# Controller.net
KiCad netlist of a schematic drawn in Altium Designer
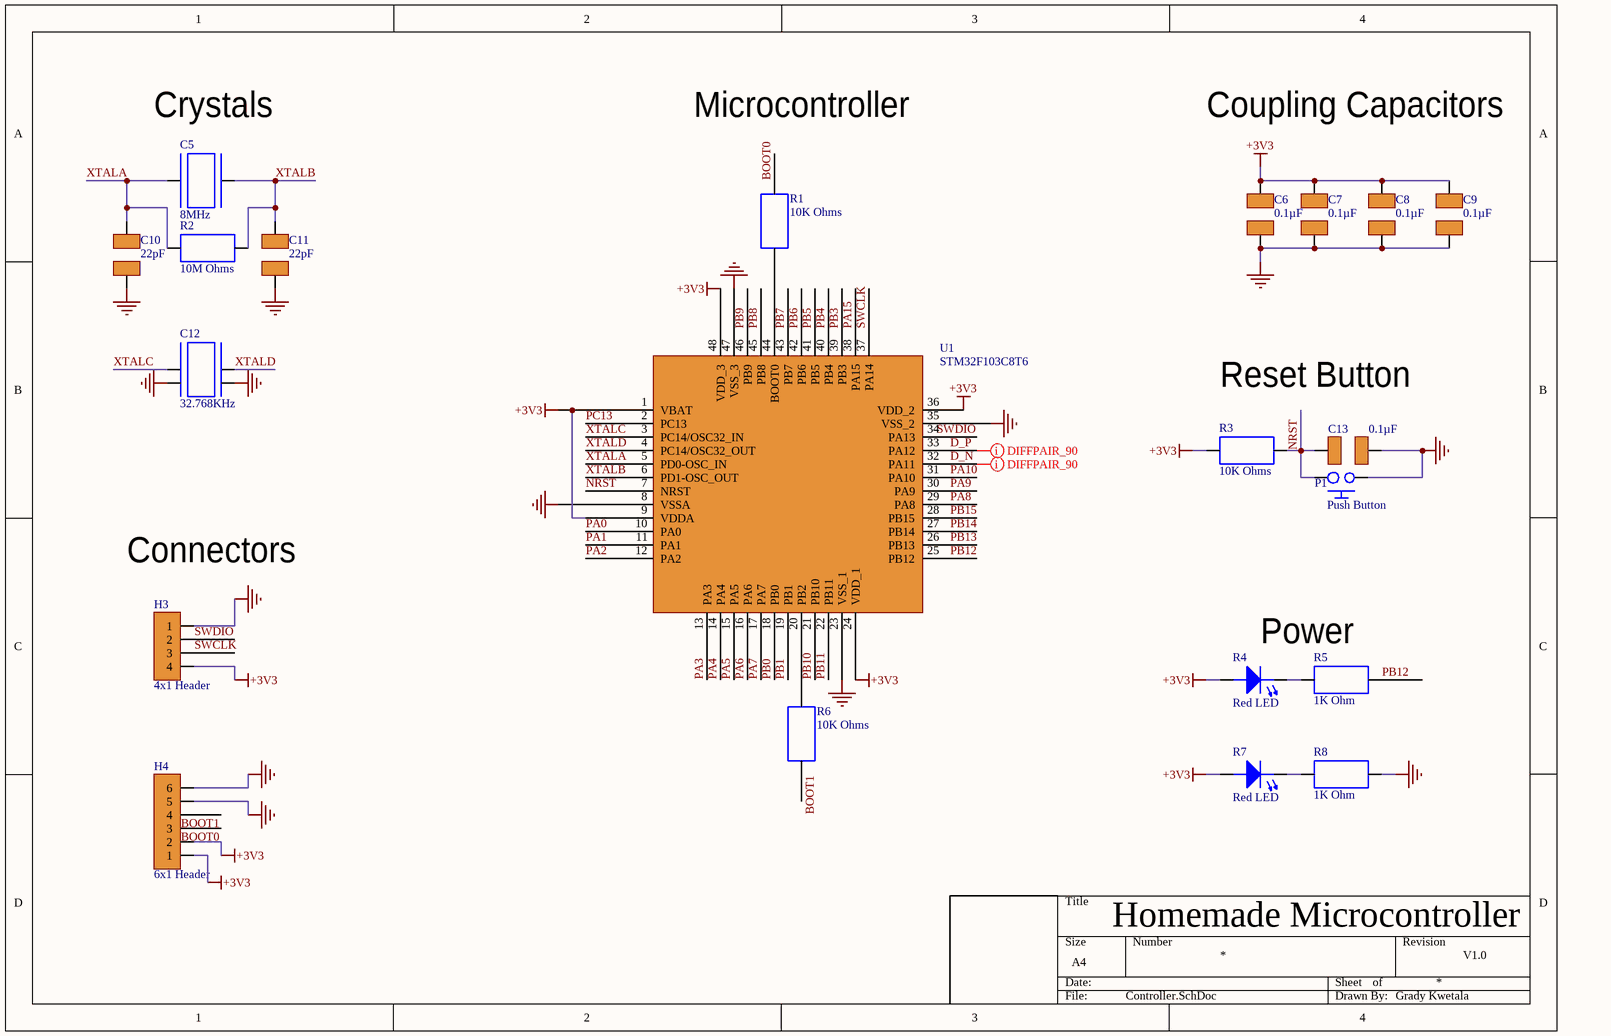
[diagram p0: Controller.SchDoc]

(export (version "E")
  (design (tool "Eeschema 10.0.6"))
  (components
    (comp (ref "C5")
      (value "8MHz")
      (footprint "Crystal 8MHz")
      (description "CRYSTAL 8.000 MHZ 20PF SMD")
      (fields
        (field (name "MANUFACTURER") "ECS International")
        (field (name "MANUFACTURER PART NUMBER") "ECS-80-20-5PX-TR")
      )
      (libsource (lib "Schematic Library") (part "ECS-80-20-5PX-TR"))
    )
    (comp (ref "C6")
      (value "0.1µF")
      (footprint "capacitor")
      (fields
        (field (name "MANUFACTURER") "KEMET")
        (field (name "MANUFACTURER PART NUMBER") "C0805C104J5RACTU")
        (field (name "TOLERANCE") "5%")
      )
      (libsource (lib "Schematic Library") (part "C0805C104J5RACTU"))
    )
    (comp (ref "C7")
      (value "0.1µF")
      (footprint "capacitor")
      (fields
        (field (name "MANUFACTURER") "KEMET")
        (field (name "MANUFACTURER PART NUMBER") "C0805C104J5RACTU")
        (field (name "TOLERANCE") "5%")
      )
      (libsource (lib "Schematic Library") (part "C0805C104J5RACTU"))
    )
    (comp (ref "C8")
      (value "0.1µF")
      (footprint "capacitor")
      (fields
        (field (name "MANUFACTURER") "KEMET")
        (field (name "MANUFACTURER PART NUMBER") "C0805C104J5RACTU")
        (field (name "TOLERANCE") "5%")
      )
      (libsource (lib "Schematic Library") (part "C0805C104J5RACTU"))
    )
    (comp (ref "C9")
      (value "0.1µF")
      (footprint "capacitor")
      (fields
        (field (name "MANUFACTURER") "KEMET")
        (field (name "MANUFACTURER PART NUMBER") "C0805C104J5RACTU")
        (field (name "TOLERANCE") "5%")
      )
      (libsource (lib "Schematic Library") (part "C0805C104J5RACTU"))
    )
    (comp (ref "C10")
      (value "22pF")
      (footprint "capacitor")
      (description "Capacitor: ceramic; MLCC; 22pF; 50VDC; C0G; ±5%; SMD; 0805")
      (fields
        (field (name "MANUFACTURER") "KEMET")
        (field (name "MANUFACTURER PART NUMBER") "C0805C220J5GACTU")
      )
      (libsource (lib "Schematic Library") (part "C0805C220J5GACTU"))
    )
    (comp (ref "C11")
      (value "22pF")
      (footprint "capacitor")
      (description "Capacitor: ceramic; MLCC; 22pF; 50VDC; C0G; ±5%; SMD; 0805")
      (fields
        (field (name "MANUFACTURER") "KEMET")
        (field (name "MANUFACTURER PART NUMBER") "C0805C220J5GACTU")
      )
      (libsource (lib "Schematic Library") (part "C0805C220J5GACTU"))
    )
    (comp (ref "C12")
      (value "32.768KHz")
      (footprint "Crystal 32KHz")
      (description "Crystals 32.768KHz 12.5pF")
      (fields
        (field (name "MANUFACTURER") "ECS International")
        (field (name "MANUFACTURER PART NUMBER") "ECS-.327-12.5-34B-C-TR")
      )
      (libsource (lib "Schematic Library") (part "ECS-.327-12.5-34B-C-TR"))
    )
    (comp (ref "C13")
      (value "0.1µF")
      (footprint "capacitor")
      (fields
        (field (name "MANUFACTURER") "KEMET")
        (field (name "MANUFACTURER PART NUMBER") "C0805C104J5RACTU")
        (field (name "TOLERANCE") "5%")
      )
      (libsource (lib "") (part "C0805C104J5RACTU_1"))
    )
    (comp (ref "H3")
      (value "4x1 Header")
      (footprint "4 Pin Header")
      (description "Conn Wire to Board HDR 4 POS 2.54mm Solder ST Thru-Hole KK® Bag")
      (fields (field (name "MANUFACTURER") "Molex") (field (name "MANUFACTURER PART NUMBER") "22-23-2041"))
      (libsource (lib "Schematic Library") (part "22-23-2041"))
    )
    (comp (ref "H4")
      (value "6x1 Header")
      (footprint "6 Pin Header")
      (description "6 Way 2.54mm Kk Molex Straight Header")
      (fields (field (name "MANUFACTURER") "Molex") (field (name "MANUFACTURER PART NUMBER") "22-27-2061"))
      (libsource (lib "Schematic Library") (part "22-27-2061"))
    )
    (comp (ref "P1")
      (value "Push Button")
      (footprint "Push Button")
      (description "SWITCH TACTILE SPST-NO 0.05A 12V")
      (fields
        (field (name "MANUFACTURER") "Wurth Electronics")
        (field (name "MANUFACTURER PART NUMBER") "430451025836")
      )
      (libsource (lib "Schematic Library") (part "430451025836"))
    )
    (comp (ref "R1")
      (value "10K Ohms")
      (footprint "Resistor")
      (description "RES SMD 10KOHM 0.1% 0.0375W 0603")
      (fields
        (field (name "MANUFACTURER") "Vishay Sfernice")
        (field (name "MANUFACTURER PART NUMBER") "PHT0603Y1002BGT")
      )
      (libsource (lib "Schematic Library") (part "PHT0603Y1002BGT"))
    )
    (comp (ref "R2")
      (value "10M Ohms")
      (footprint "Resistor")
      (description "RES SMD 10M OHM 5% 1/8W 0805")
      (fields
        (field (name "MANUFACTURER") "Ohmite")
        (field (name "MANUFACTURER PART NUMBER") "HVC0805T1005JET")
      )
      (libsource (lib "Schematic Library") (part "HVC0805T1005JET"))
    )
    (comp (ref "R3")
      (value "10K Ohms")
      (footprint "Resistor")
      (description "RES SMD 10KOHM 0.1% 0.0375W 0603")
      (fields
        (field (name "MANUFACTURER") "Vishay Sfernice")
        (field (name "MANUFACTURER PART NUMBER") "PHT0603Y1002BGT")
      )
      (libsource (lib "Schematic Library") (part "PHT0603Y1002BGT"))
    )
    (comp (ref "R4")
      (value "Red LED")
      (footprint "LED")
      (description "LED RED DIFFUSED 0805 SMD")
      (fields
        (field (name "MANUFACTURER") "Osram Opto")
        (field (name "MANUFACTURER PART NUMBER") "LHR974-LP-1")
      )
      (libsource (lib "Schematic Library") (part "LHR974-LP-1"))
    )
    (comp (ref "R5")
      (value "1K Ohm")
      (footprint "Resistor")
      (fields
        (field (name "MANUFACTURER") "TE Connectivity")
        (field (name "MANUFACTURER PART NUMBER") "CRGP2512F1K0")
        (field (name "TOLERANCE") "1%")
      )
      (libsource (lib "Schematic Library") (part "CRGP2512F1K0"))
    )
    (comp (ref "R6")
      (value "10K Ohms")
      (footprint "Resistor")
      (description "RES SMD 10KOHM 0.1% 0.0375W 0603")
      (fields
        (field (name "MANUFACTURER") "Vishay Sfernice")
        (field (name "MANUFACTURER PART NUMBER") "PHT0603Y1002BGT")
      )
      (libsource (lib "Schematic Library") (part "PHT0603Y1002BGT"))
    )
    (comp (ref "R7")
      (value "Red LED")
      (footprint "LED")
      (description "LED RED DIFFUSED 0805 SMD")
      (fields
        (field (name "MANUFACTURER") "Osram Opto")
        (field (name "MANUFACTURER PART NUMBER") "LHR974-LP-1")
      )
      (libsource (lib "Schematic Library") (part "LHR974-LP-1"))
    )
    (comp (ref "R8")
      (value "1K Ohm")
      (footprint "Resistor")
      (fields
        (field (name "MANUFACTURER") "TE Connectivity")
        (field (name "MANUFACTURER PART NUMBER") "CRGP2512F1K0")
        (field (name "TOLERANCE") "1%")
      )
      (libsource (lib "Schematic Library") (part "CRGP2512F1K0"))
    )
    (comp (ref "U1")
      (value "STM32F103C8T6")
      (footprint "Micro controller")
      (fields (field (name "MANUFACTURER") "STMicroelectronics"))
      (libsource (lib "Schematic Library") (part "STM32F103C8T6"))
    )
  )
  (nets
    (net (code "1") (name "+3V3") (class "Default")
      (node (ref "C6") (pin "2") (pinfunction "2_2") (pintype "passive"))
      (node (ref "C7") (pin "2") (pinfunction "2_2") (pintype "passive"))
      (node (ref "C8") (pin "2") (pinfunction "2_2") (pintype "passive"))
      (node (ref "C9") (pin "2") (pinfunction "2_2") (pintype "passive"))
      (node (ref "H3") (pin "4") (pinfunction "4_4") (pintype "passive"))
      (node (ref "H4") (pin "1") (pinfunction "1_1") (pintype "passive"))
      (node (ref "H4") (pin "2") (pinfunction "2_2") (pintype "passive"))
      (node (ref "R3") (pin "2") (pinfunction "2_2") (pintype "passive"))
      (node (ref "R4") (pin "2") (pinfunction "2_2") (pintype "passive"))
      (node (ref "R7") (pin "2") (pinfunction "2_2") (pintype "passive"))
      (node (ref "U1") (pin "1") (pinfunction "VBAT_1") (pintype "passive"))
      (node (ref "U1") (pin "24") (pinfunction "VDD_1_24") (pintype "passive"))
      (node (ref "U1") (pin "36") (pinfunction "VDD_2_36") (pintype "passive"))
      (node (ref "U1") (pin "48") (pinfunction "VDD_3_48") (pintype "passive"))
      (node (ref "U1") (pin "9") (pinfunction "VDDA_9") (pintype "passive"))
    )
    (net (code "2") (name "/BOOT0") (class "Default")
      (node (ref "H4") (pin "3") (pinfunction "3_3") (pintype "passive"))
      (node (ref "R1") (pin "2") (pinfunction "2_2") (pintype "passive"))
    )
    (net (code "3") (name "/BOOT1") (class "Default")
      (node (ref "H4") (pin "4") (pinfunction "4_4") (pintype "passive"))
      (node (ref "R6") (pin "1") (pinfunction "1_1") (pintype "passive"))
    )
    (net (code "4") (name "/D_N") (class "Default")
      (node (ref "U1") (pin "32") (pinfunction "PA11_32") (pintype "passive"))
    )
    (net (code "5") (name "/D_P") (class "Default")
      (node (ref "U1") (pin "33") (pinfunction "PA12_33") (pintype "passive"))
    )
    (net (code "6") (name "/NRST") (class "Default")
      (node (ref "C13") (pin "2") (pinfunction "2_2") (pintype "passive"))
      (node (ref "P1") (pin "2") (pinfunction "2_2") (pintype "passive"))
      (node (ref "R3") (pin "1") (pinfunction "1_1") (pintype "passive"))
      (node (ref "U1") (pin "7") (pinfunction "NRST_7") (pintype "passive"))
    )
    (net (code "7") (name "/PA0") (class "Default")
      (node (ref "U1") (pin "10") (pinfunction "PA0_10") (pintype "passive"))
    )
    (net (code "8") (name "/PA1") (class "Default")
      (node (ref "U1") (pin "11") (pinfunction "PA1_11") (pintype "passive"))
    )
    (net (code "9") (name "/PA2") (class "Default")
      (node (ref "U1") (pin "12") (pinfunction "PA2_12") (pintype "passive"))
    )
    (net (code "10") (name "/PA3") (class "Default")
      (node (ref "U1") (pin "13") (pinfunction "PA3_13") (pintype "passive"))
    )
    (net (code "11") (name "/PA4") (class "Default")
      (node (ref "U1") (pin "14") (pinfunction "PA4_14") (pintype "passive"))
    )
    (net (code "12") (name "/PA5") (class "Default")
      (node (ref "U1") (pin "15") (pinfunction "PA5_15") (pintype "passive"))
    )
    (net (code "13") (name "/PA6") (class "Default")
      (node (ref "U1") (pin "16") (pinfunction "PA6_16") (pintype "passive"))
    )
    (net (code "14") (name "/PA7") (class "Default")
      (node (ref "U1") (pin "17") (pinfunction "PA7_17") (pintype "passive"))
    )
    (net (code "15") (name "/PA8") (class "Default")
      (node (ref "U1") (pin "29") (pinfunction "PA8_29") (pintype "passive"))
    )
    (net (code "16") (name "/PA9") (class "Default")
      (node (ref "U1") (pin "30") (pinfunction "PA9_30") (pintype "passive"))
    )
    (net (code "17") (name "/PA10") (class "Default")
      (node (ref "U1") (pin "31") (pinfunction "PA10_31") (pintype "passive"))
    )
    (net (code "18") (name "/PA15") (class "Default")
      (node (ref "U1") (pin "38") (pinfunction "PA15_38") (pintype "passive"))
    )
    (net (code "19") (name "/PB0") (class "Default")
      (node (ref "U1") (pin "18") (pinfunction "PB0_18") (pintype "passive"))
    )
    (net (code "20") (name "/PB1") (class "Default")
      (node (ref "U1") (pin "19") (pinfunction "PB1_19") (pintype "passive"))
    )
    (net (code "21") (name "/PB3") (class "Default")
      (node (ref "U1") (pin "39") (pinfunction "PB3_39") (pintype "passive"))
    )
    (net (code "22") (name "/PB4") (class "Default")
      (node (ref "U1") (pin "40") (pinfunction "PB4_40") (pintype "passive"))
    )
    (net (code "23") (name "/PB5") (class "Default")
      (node (ref "U1") (pin "41") (pinfunction "PB5_41") (pintype "passive"))
    )
    (net (code "24") (name "/PB6") (class "Default")
      (node (ref "U1") (pin "42") (pinfunction "PB6_42") (pintype "passive"))
    )
    (net (code "25") (name "/PB7") (class "Default")
      (node (ref "U1") (pin "43") (pinfunction "PB7_43") (pintype "passive"))
    )
    (net (code "26") (name "/PB8") (class "Default")
      (node (ref "U1") (pin "45") (pinfunction "PB8_45") (pintype "passive"))
    )
    (net (code "27") (name "/PB9") (class "Default")
      (node (ref "U1") (pin "46") (pinfunction "PB9_46") (pintype "passive"))
    )
    (net (code "28") (name "/PB10") (class "Default")
      (node (ref "U1") (pin "21") (pinfunction "PB10_21") (pintype "passive"))
    )
    (net (code "29") (name "/PB11") (class "Default")
      (node (ref "U1") (pin "22") (pinfunction "PB11_22") (pintype "passive"))
    )
    (net (code "30") (name "/PB12") (class "Default")
      (node (ref "R5") (pin "1") (pinfunction "1_1") (pintype "passive"))
      (node (ref "U1") (pin "25") (pinfunction "PB12_25") (pintype "passive"))
    )
    (net (code "31") (name "/PB13") (class "Default")
      (node (ref "U1") (pin "26") (pinfunction "PB13_26") (pintype "passive"))
    )
    (net (code "32") (name "/PB14") (class "Default")
      (node (ref "U1") (pin "27") (pinfunction "PB14_27") (pintype "passive"))
    )
    (net (code "33") (name "/PB15") (class "Default")
      (node (ref "U1") (pin "28") (pinfunction "PB15_28") (pintype "passive"))
    )
    (net (code "34") (name "/PC13") (class "Default")
      (node (ref "U1") (pin "2") (pinfunction "PC13_2") (pintype "passive"))
    )
    (net (code "35") (name "/SWCLK") (class "Default")
      (node (ref "H3") (pin "3") (pinfunction "3_3") (pintype "passive"))
      (node (ref "U1") (pin "37") (pinfunction "PA14_37") (pintype "passive"))
    )
    (net (code "36") (name "/SWDIO") (class "Default")
      (node (ref "H3") (pin "2") (pinfunction "2_2") (pintype "passive"))
      (node (ref "U1") (pin "34") (pinfunction "PA13_34") (pintype "passive"))
    )
    (net (code "37") (name "/XTALA") (class "Default")
      (node (ref "C10") (pin "2") (pinfunction "2_2") (pintype "passive"))
      (node (ref "C5") (pin "1") (pinfunction "1_1") (pintype "passive"))
      (node (ref "R2") (pin "1") (pinfunction "1_1") (pintype "passive"))
      (node (ref "U1") (pin "5") (pinfunction "PD0-OSC_IN_5") (pintype "passive"))
    )
    (net (code "38") (name "/XTALB") (class "Default")
      (node (ref "C11") (pin "2") (pinfunction "2_2") (pintype "passive"))
      (node (ref "C5") (pin "2") (pinfunction "2_2") (pintype "passive"))
      (node (ref "R2") (pin "2") (pinfunction "2_2") (pintype "passive"))
      (node (ref "U1") (pin "6") (pinfunction "PD1-OSC_OUT_6") (pintype "passive"))
    )
    (net (code "39") (name "/XTALC") (class "Default")
      (node (ref "C12") (pin "1") (pinfunction "1_1") (pintype "passive"))
      (node (ref "U1") (pin "3") (pinfunction "PC14/OSC32_IN_3") (pintype "passive"))
    )
    (net (code "40") (name "/XTALD") (class "Default")
      (node (ref "C12") (pin "2") (pinfunction "2_2") (pintype "passive"))
      (node (ref "U1") (pin "4") (pinfunction "PC14/OSC32_OUT_4") (pintype "passive"))
    )
    (net (code "41") (name "GND") (class "Default")
      (node (ref "C10") (pin "1") (pinfunction "1_1") (pintype "passive"))
      (node (ref "C11") (pin "1") (pinfunction "1_1") (pintype "passive"))
      (node (ref "C12") (pin "3") (pinfunction "3_3") (pintype "passive"))
      (node (ref "C12") (pin "4") (pinfunction "4_4") (pintype "passive"))
      (node (ref "C13") (pin "1") (pinfunction "1_1") (pintype "passive"))
      (node (ref "C6") (pin "1") (pinfunction "1_1") (pintype "passive"))
      (node (ref "C7") (pin "1") (pinfunction "1_1") (pintype "passive"))
      (node (ref "C8") (pin "1") (pinfunction "1_1") (pintype "passive"))
      (node (ref "C9") (pin "1") (pinfunction "1_1") (pintype "passive"))
      (node (ref "H3") (pin "1") (pinfunction "1_1") (pintype "passive"))
      (node (ref "H4") (pin "5") (pinfunction "5_5") (pintype "passive"))
      (node (ref "H4") (pin "6") (pinfunction "6_6") (pintype "passive"))
      (node (ref "P1") (pin "1") (pinfunction "1_1") (pintype "passive"))
      (node (ref "R8") (pin "1") (pinfunction "1_1") (pintype "passive"))
      (node (ref "U1") (pin "23") (pinfunction "VSS_1_23") (pintype "passive"))
      (node (ref "U1") (pin "35") (pinfunction "VSS_2_35") (pintype "passive"))
      (node (ref "U1") (pin "47") (pinfunction "VSS_3_47") (pintype "passive"))
      (node (ref "U1") (pin "8") (pinfunction "VSSA_8") (pintype "passive"))
    )
    (net (code "42") (name "Net-(R4-Pad1)") (class "Default")
      (node (ref "R4") (pin "1") (pinfunction "1_1") (pintype "passive"))
      (node (ref "R5") (pin "2") (pinfunction "2_2") (pintype "passive"))
    )
    (net (code "43") (name "Net-(R7-Pad1)") (class "Default")
      (node (ref "R7") (pin "1") (pinfunction "1_1") (pintype "passive"))
      (node (ref "R8") (pin "2") (pinfunction "2_2") (pintype "passive"))
    )
    (net (code "44") (name "Net-(U1-BOOT0)") (class "Default")
      (node (ref "R1") (pin "1") (pinfunction "1_1") (pintype "passive"))
      (node (ref "U1") (pin "44") (pinfunction "BOOT0_44") (pintype "passive"))
    )
    (net (code "45") (name "Net-(U1-PB2)") (class "Default")
      (node (ref "R6") (pin "2") (pinfunction "2_2") (pintype "passive"))
      (node (ref "U1") (pin "20") (pinfunction "PB2_20") (pintype "passive"))
    )
  )
)
